# RS485.net
KiCad netlist of a schematic drawn in Altium Designer
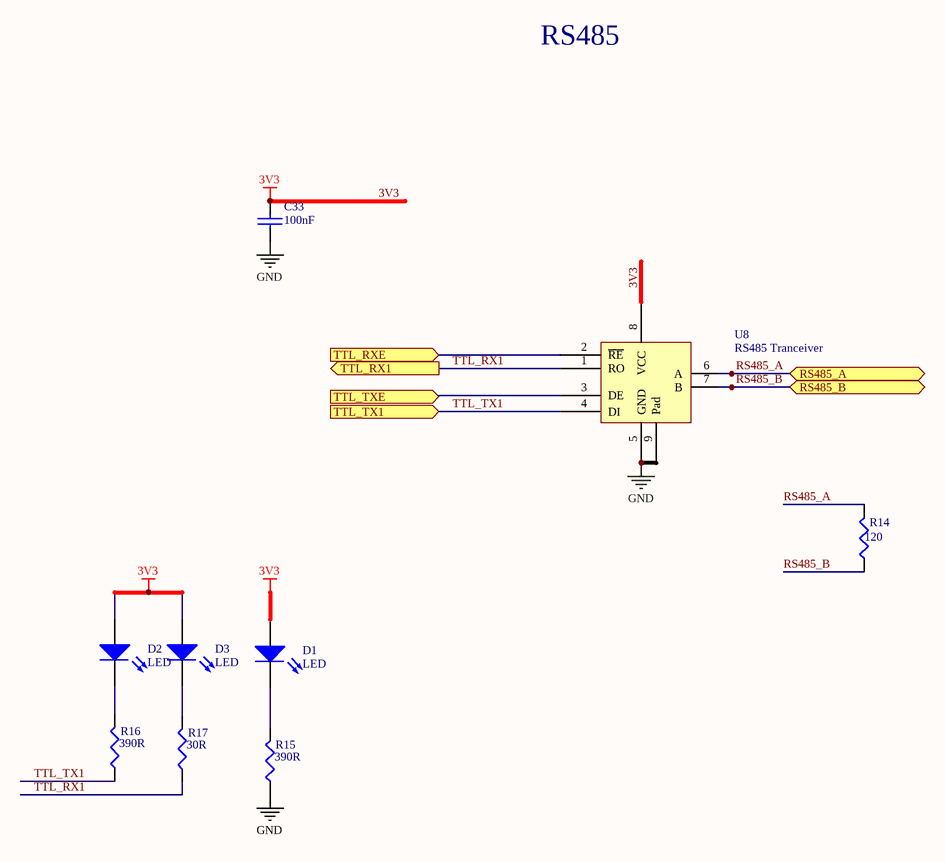
[diagram p0: RS485.SchDoc]

(export (version "E")
  (design (tool "Eeschema 10.0.6"))
  (components
    (comp (ref "C33")
      (value "100nF")
      (footprint "CAP0402")
      (description "Capacitor")
      (fields
        (field (name "MANUFACTURER") "TDK Corporation")
        (field (name "MANUFACTURER PART NUMBER") "CGA2B3X7R1V104K050BB")
      )
      (libsource (lib "BPL-ShematicLibrary") (part "Capacitor"))
    )
    (comp (ref "D1")
      (value "LED")
      (footprint "LED-0603-RED")
      (fields
        (field (name "MANUFACTURER") "Wurth Electronics Inc.")
        (field (name "MANUFACTURER PART NUMBER") "150060RS75000")
      )
      (libsource (lib "BPL-ShematicLibrary") (part "LED"))
    )
    (comp (ref "D2")
      (value "LED")
      (footprint "LED-0603-YELLOW")
      (fields
        (field (name "MANUFACTURER") "Wurth Electronics Inc.")
        (field (name "MANUFACTURER PART NUMBER") "150060YS75000")
      )
      (libsource (lib "BPL-ShematicLibrary") (part "LED"))
    )
    (comp (ref "D3")
      (value "LED")
      (footprint "LED-0603-GREEN")
      (fields
        (field (name "MANUFACTURER") "Wurth Electronics Inc.")
        (field (name "MANUFACTURER PART NUMBER") "150060GS75000")
      )
      (libsource (lib "BPL-ShematicLibrary") (part "LED"))
    )
    (comp (ref "R14")
      (value "120")
      (footprint "RES1206")
      (description "Resistor")
      (fields (field (name "Comment") "Res"))
      (libsource (lib "BPL-ShematicLibrary") (part "Resistor"))
    )
    (comp (ref "R15")
      (value "390R")
      (footprint "RES0402")
      (description "Resistor")
      (fields
        (field (name "MANUFACTURER") "Yageo")
        (field (name "MANUFACTURER PART NUMBER") "RC0402FR-07390RL")
      )
      (libsource (lib "BPL-ShematicLibrary") (part "Resistor"))
    )
    (comp (ref "R16")
      (value "390R")
      (footprint "RES0402")
      (description "Resistor")
      (fields
        (field (name "MANUFACTURER") "Yageo")
        (field (name "MANUFACTURER PART NUMBER") "RC0402FR-07390RL")
      )
      (libsource (lib "BPL-ShematicLibrary") (part "Resistor"))
    )
    (comp (ref "R17")
      (value "30R")
      (footprint "RES0402")
      (description "Resistor")
      (fields
        (field (name "MANUFACTURER") "Yageo")
        (field (name "MANUFACTURER PART NUMBER") "RC0402FR-0730RL")
      )
      (libsource (lib "BPL-ShematicLibrary") (part "Resistor"))
    )
    (comp (ref "U8")
      (value "RS485 Tranceiver")
      (footprint "MAX22501EATA+")
      (fields
        (field (name "MANUFACTURER PART NUMBER") "MAX22501EATA+")
        (field (name "MANUFACTURER") "Maxim Integrated")
      )
      (libsource (lib "BPL-ShematicLibrary") (part "MAX22501EATA+"))
    )
  )
  (nets
    (net (code "1") (name "/RS485_A") (class "Default")
      (node (ref "R14") (pin "2") (pinfunction "2_2") (pintype "passive"))
      (node (ref "U8") (pin "6") (pinfunction "A_6") (pintype "passive"))
    )
    (net (code "2") (name "/RS485_B") (class "Default")
      (node (ref "R14") (pin "1") (pinfunction "1_1") (pintype "passive"))
      (node (ref "U8") (pin "7") (pinfunction "B_7") (pintype "passive"))
    )
    (net (code "3") (name "/TTL_RX1") (class "Default")
      (node (ref "R17") (pin "1") (pinfunction "1_1") (pintype "passive"))
      (node (ref "U8") (pin "1") (pinfunction "RO_1") (pintype "passive"))
    )
    (net (code "4") (name "/TTL_RXE") (class "Default")
      (node (ref "U8") (pin "2") (pinfunction "~{RE}_2") (pintype "passive"))
    )
    (net (code "5") (name "/TTL_TX1") (class "Default")
      (node (ref "R16") (pin "1") (pinfunction "1_1") (pintype "passive"))
      (node (ref "U8") (pin "4") (pinfunction "DI_4") (pintype "passive"))
    )
    (net (code "6") (name "/TTL_TXE") (class "Default")
      (node (ref "U8") (pin "3") (pinfunction "DE_3") (pintype "passive"))
    )
    (net (code "7") (name "3V3") (class "Default")
      (node (ref "C33") (pin "1") (pinfunction "1_1") (pintype "passive"))
      (node (ref "D1") (pin "2") (pinfunction "2_2") (pintype "passive"))
      (node (ref "D2") (pin "2") (pinfunction "2_2") (pintype "passive"))
      (node (ref "D3") (pin "2") (pinfunction "2_2") (pintype "passive"))
      (node (ref "U8") (pin "8") (pinfunction "VCC_8") (pintype "passive"))
    )
    (net (code "8") (name "GND") (class "Default")
      (node (ref "C33") (pin "2") (pinfunction "2_2") (pintype "passive"))
      (node (ref "R15") (pin "1") (pinfunction "1_1") (pintype "passive"))
      (node (ref "U8") (pin "5") (pinfunction "GND_5") (pintype "passive"))
      (node (ref "U8") (pin "9") (pinfunction "Pad_9") (pintype "passive"))
    )
    (net (code "9") (name "Net-(D1-Pad1)") (class "Default")
      (node (ref "D1") (pin "1") (pinfunction "1_1") (pintype "passive"))
      (node (ref "R15") (pin "2") (pinfunction "2_2") (pintype "passive"))
    )
    (net (code "10") (name "Net-(D2-Pad1)") (class "Default")
      (node (ref "D2") (pin "1") (pinfunction "1_1") (pintype "passive"))
      (node (ref "R16") (pin "2") (pinfunction "2_2") (pintype "passive"))
    )
    (net (code "11") (name "Net-(D3-Pad1)") (class "Default")
      (node (ref "D3") (pin "1") (pinfunction "1_1") (pintype "passive"))
      (node (ref "R17") (pin "2") (pinfunction "2_2") (pintype "passive"))
    )
  )
)
